# keg-scale.net
KiCad netlist of a schematic drawn in EAGLE
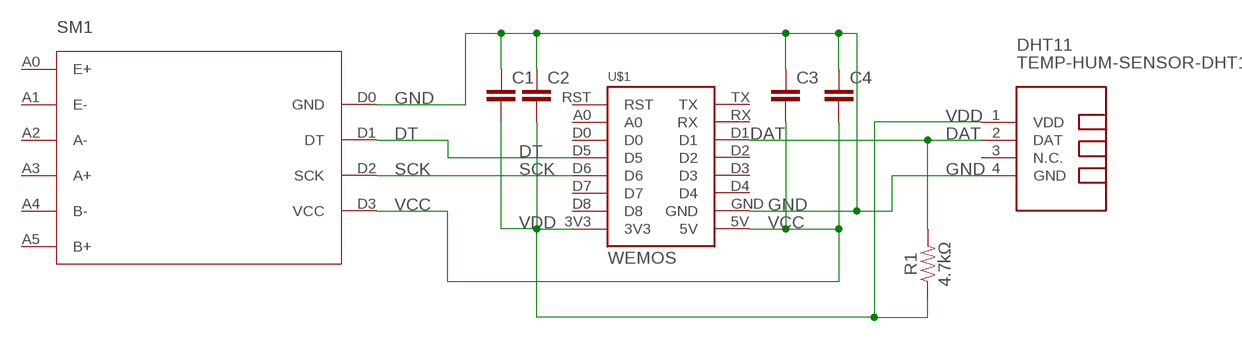
[diagram p0: schematic, sheet 1]

(export (version "E")
  (design (tool "Eeschema 10.0.6"))
  (components
    (comp (ref "C1")
      (value "C5/3")
      (footprint "eagle-import:C5B3")
      (libsource (lib "eagle-import") (part "C5/3"))
    )
    (comp (ref "C2")
      (value "C5/3")
      (footprint "eagle-import:C5B3")
      (libsource (lib "eagle-import") (part "C5/3"))
    )
    (comp (ref "C3")
      (value "C5/3")
      (footprint "eagle-import:C5B3")
      (libsource (lib "eagle-import") (part "C5/3"))
    )
    (comp (ref "C4")
      (value "C5/3")
      (footprint "eagle-import:C5B3")
      (libsource (lib "eagle-import") (part "C5/3"))
    )
    (comp (ref "DHT11")
      (value "TEMP-HUM-SENSOR-DHT11")
      (footprint "eagle-import:TEMP-HUM-SENSOR-DHT11")
      (fields
        (field (name "URL") "https://randomnerdtutorials.com/esp8266-dht11dht22-temperature-and-humidity-web-server-with-arduino-ide/")
      )
      (libsource (lib "eagle-import") (part "TEMP-HUM-SENSOR-DHT11"))
    )
    (comp (ref "R1")
      (value "4.7kΩ")
      (footprint "eagle-import:AXIAL-0.3")
      (libsource (lib "eagle-import") (part "RESISTORAXIAL-0.3"))
    )
    (comp (ref "SM1")
      (value "HX711")
      (footprint "eagle-import:HX711")
      (fields (field (name "URL") "https://how2electronics.com/iot-weighing-scale-hx711-load-cell-esp8266/"))
      (libsource (lib "eagle-import") (part "HX711"))
    )
    (comp (ref "U$1")
      (value "WEMOS")
      (footprint "eagle-import:WEMOS")
      (libsource (lib "eagle-import") (part "WEMOS"))
    )
  )
  (nets
    (net (code "1") (name "/DAT") (class "Default")
      (node (ref "DHT11") (pin "2") (pinfunction "DAT_2") (pintype "bidirectional"))
      (node (ref "R1") (pin "P$2") (pinfunction "2_P$2") (pintype "passive"))
      (node (ref "U$1") (pin "D1") (pinfunction "D1_D1") (pintype "bidirectional"))
    )
    (net (code "2") (name "/DT") (class "Default")
      (node (ref "SM1") (pin "D1") (pinfunction "DT_D1") (pintype "bidirectional"))
      (node (ref "U$1") (pin "D5") (pinfunction "D5_D5") (pintype "bidirectional"))
    )
    (net (code "3") (name "/GND") (class "Default")
      (node (ref "C1") (pin "1") (pinfunction "1_1") (pintype "passive"))
      (node (ref "C2") (pin "1") (pinfunction "1_1") (pintype "passive"))
      (node (ref "C3") (pin "1") (pinfunction "1_1") (pintype "passive"))
      (node (ref "C4") (pin "1") (pinfunction "1_1") (pintype "passive"))
      (node (ref "DHT11") (pin "4") (pinfunction "GND_4") (pintype "power_in"))
      (node (ref "SM1") (pin "D0") (pinfunction "GND_D0") (pintype "bidirectional"))
      (node (ref "U$1") (pin "GND") (pinfunction "GND_GND") (pintype "bidirectional"))
    )
    (net (code "4") (name "/SCK") (class "Default")
      (node (ref "SM1") (pin "D2") (pinfunction "SCK_D2") (pintype "bidirectional"))
      (node (ref "U$1") (pin "D6") (pinfunction "D6_D6") (pintype "bidirectional"))
    )
    (net (code "5") (name "/VCC") (class "Default")
      (node (ref "C3") (pin "2") (pinfunction "2_2") (pintype "passive"))
      (node (ref "C4") (pin "2") (pinfunction "2_2") (pintype "passive"))
      (node (ref "SM1") (pin "D3") (pinfunction "VCC_D3") (pintype "bidirectional"))
      (node (ref "U$1") (pin "5V") (pinfunction "5V_5V") (pintype "bidirectional"))
    )
    (net (code "6") (name "/VDD") (class "Default")
      (node (ref "C1") (pin "2") (pinfunction "2_2") (pintype "passive"))
      (node (ref "C2") (pin "2") (pinfunction "2_2") (pintype "passive"))
      (node (ref "DHT11") (pin "1") (pinfunction "VDD_1") (pintype "power_in"))
      (node (ref "R1") (pin "P$1") (pinfunction "1_P$1") (pintype "passive"))
      (node (ref "U$1") (pin "3V3") (pinfunction "3V3_3V3") (pintype "bidirectional"))
    )
    (net (code "7") (name "unconnected-(DHT11-N.C.-Pad3)") (class "Default")
      (node (ref "DHT11") (pin "3") (pinfunction "N.C._3") (pintype "passive"))
    )
    (net (code "8") (name "unconnected-(SM1-A+-PadA3)") (class "Default")
      (node (ref "SM1") (pin "A3") (pinfunction "A+_A3") (pintype "bidirectional"))
    )
    (net (code "9") (name "unconnected-(SM1-A--PadA2)") (class "Default")
      (node (ref "SM1") (pin "A2") (pinfunction "A-_A2") (pintype "bidirectional"))
    )
    (net (code "10") (name "unconnected-(SM1-B+-PadA5)") (class "Default")
      (node (ref "SM1") (pin "A5") (pinfunction "B+_A5") (pintype "bidirectional"))
    )
    (net (code "11") (name "unconnected-(SM1-B--PadA4)") (class "Default")
      (node (ref "SM1") (pin "A4") (pinfunction "B-_A4") (pintype "bidirectional"))
    )
    (net (code "12") (name "unconnected-(SM1-E+-PadA0)") (class "Default")
      (node (ref "SM1") (pin "A0") (pinfunction "E+_A0") (pintype "bidirectional"))
    )
    (net (code "13") (name "unconnected-(SM1-E--PadA1)") (class "Default")
      (node (ref "SM1") (pin "A1") (pinfunction "E-_A1") (pintype "bidirectional"))
    )
    (net (code "14") (name "unconnected-(U$1-PadA0)") (class "Default")
      (node (ref "U$1") (pin "A0") (pinfunction "A0_A0") (pintype "bidirectional"))
    )
    (net (code "15") (name "unconnected-(U$1-PadD0)") (class "Default")
      (node (ref "U$1") (pin "D0") (pinfunction "D0_D0") (pintype "bidirectional"))
    )
    (net (code "16") (name "unconnected-(U$1-PadD2)") (class "Default")
      (node (ref "U$1") (pin "D2") (pinfunction "D2_D2") (pintype "bidirectional"))
    )
    (net (code "17") (name "unconnected-(U$1-PadD3)") (class "Default")
      (node (ref "U$1") (pin "D3") (pinfunction "D3_D3") (pintype "bidirectional"))
    )
    (net (code "18") (name "unconnected-(U$1-PadD4)") (class "Default")
      (node (ref "U$1") (pin "D4") (pinfunction "D4_D4") (pintype "bidirectional"))
    )
    (net (code "19") (name "unconnected-(U$1-PadD7)") (class "Default")
      (node (ref "U$1") (pin "D7") (pinfunction "D7_D7") (pintype "bidirectional"))
    )
    (net (code "20") (name "unconnected-(U$1-PadD8)") (class "Default")
      (node (ref "U$1") (pin "D8") (pinfunction "D8_D8") (pintype "bidirectional"))
    )
    (net (code "21") (name "unconnected-(U$1-PadRST)") (class "Default")
      (node (ref "U$1") (pin "RST") (pinfunction "RST_RST") (pintype "bidirectional"))
    )
    (net (code "22") (name "unconnected-(U$1-PadRX)") (class "Default")
      (node (ref "U$1") (pin "RX") (pinfunction "RX_RX") (pintype "bidirectional"))
    )
    (net (code "23") (name "unconnected-(U$1-PadTX)") (class "Default")
      (node (ref "U$1") (pin "TX") (pinfunction "TX_TX") (pintype "bidirectional"))
    )
  )
)
